# SparkFun_WiFi_Shield_-_DA16200.net
KiCad netlist of a schematic drawn in EAGLE
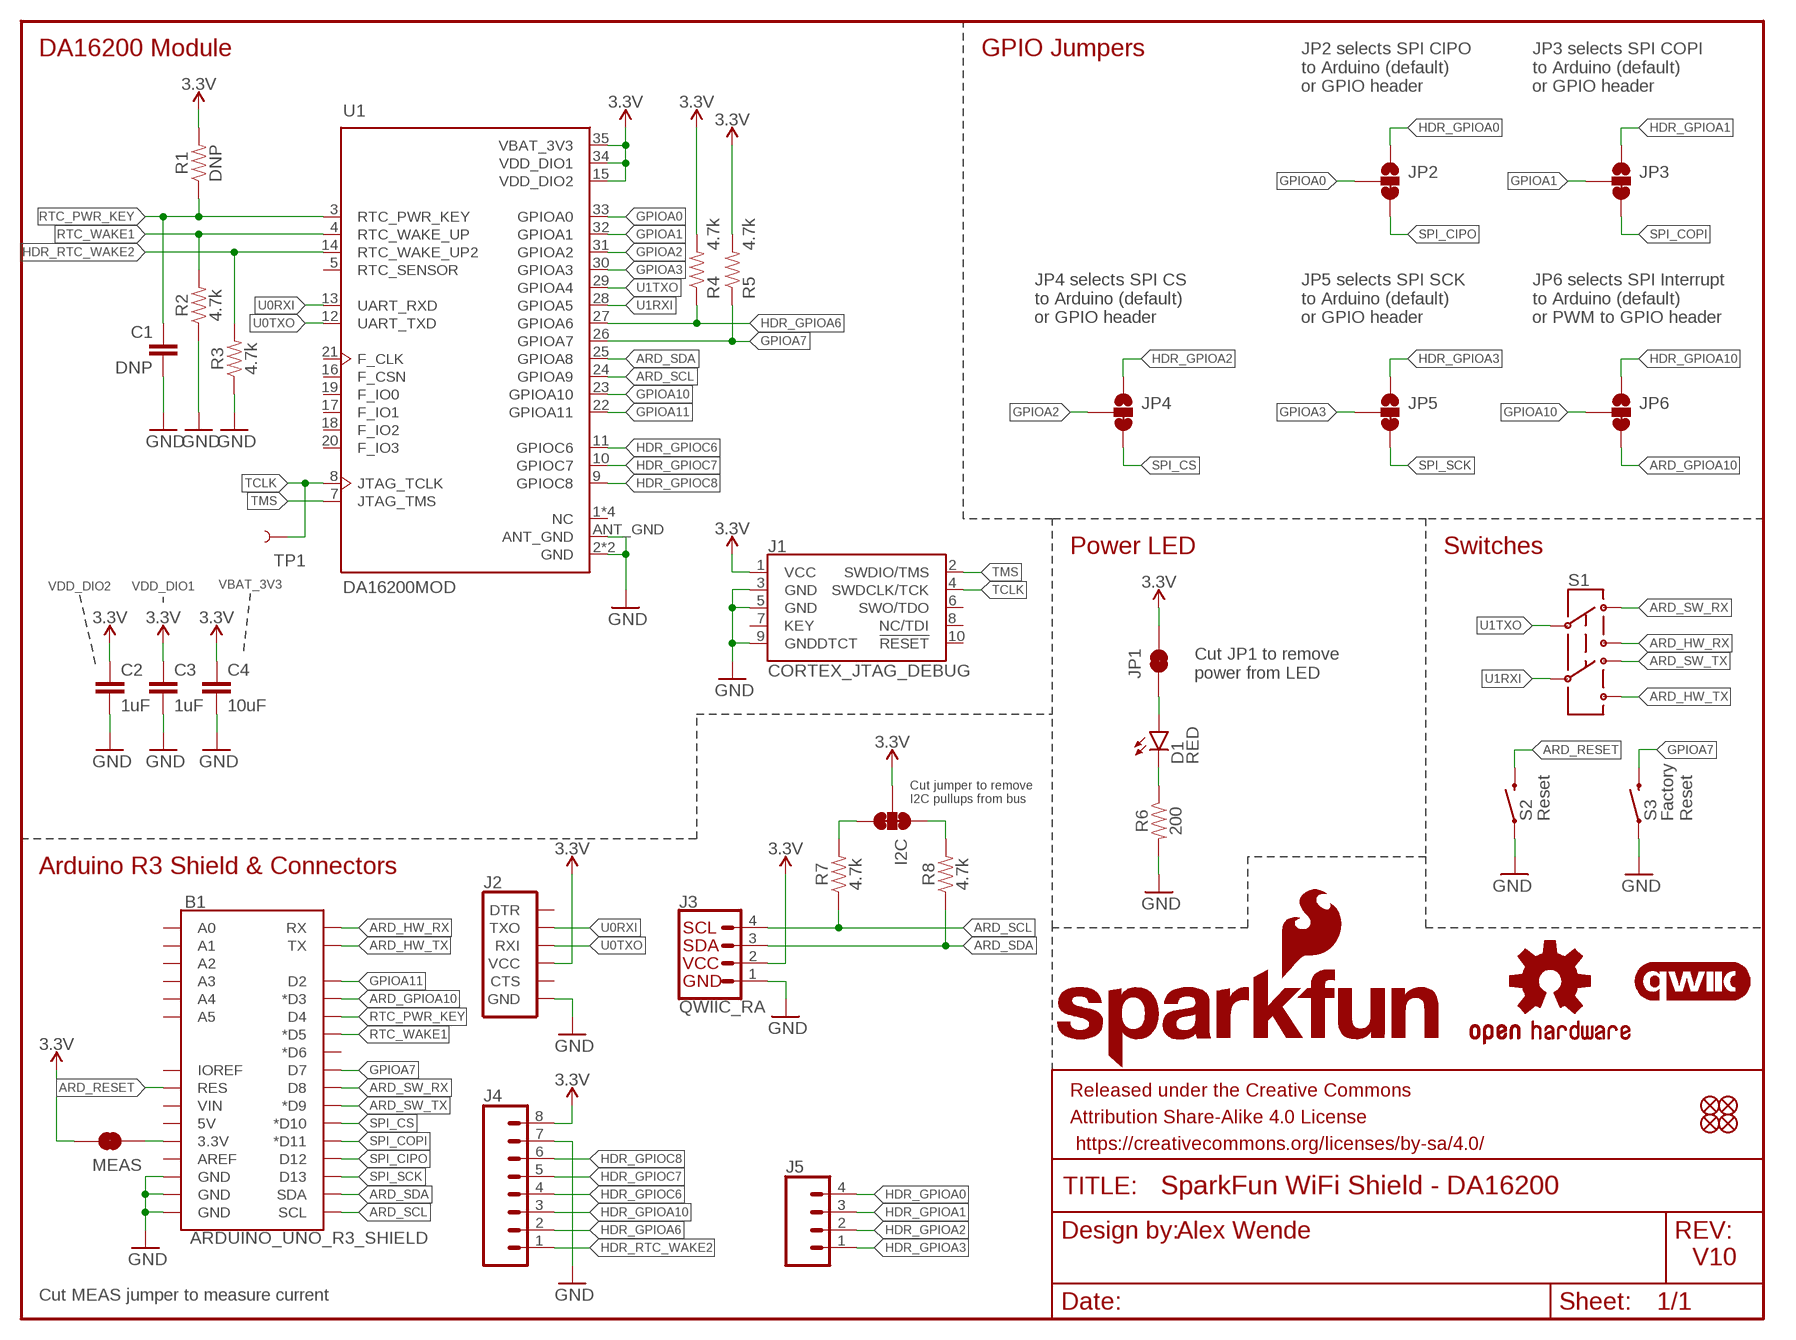
[diagram p0: schematic, sheet 1]

(export (version "E")
  (design (tool "Eeschema 10.0.6"))
  (components
    (comp (ref "B1")
      (value "ARDUINO_UNO_R3_SHIELD")
      (footprint "eagle-import:UNO_R3_SHIELD_NOLABELS_LOCK")
      (libsource (lib "eagle-import") (part "ARDUINO_UNO_R3_SHIELDUNO_R3_SHIELD_NOLABELS_LOCK"))
    )
    (comp (ref "C1")
      (value "DNP")
      (footprint "eagle-import:0603")
      (libsource (lib "eagle-import") (part "CAP-0603"))
    )
    (comp (ref "C2")
      (value "1uF")
      (footprint "eagle-import:0603")
      (libsource (lib "eagle-import") (part "1.0UF-0603-16V-10%"))
    )
    (comp (ref "C3")
      (value "1uF")
      (footprint "eagle-import:0603")
      (libsource (lib "eagle-import") (part "1.0UF-0603-16V-10%"))
    )
    (comp (ref "C4")
      (value "10uF")
      (footprint "eagle-import:0603")
      (libsource (lib "eagle-import") (part "10UF-0603-6.3V-20%"))
    )
    (comp (ref "D1")
      (value "RED")
      (footprint "eagle-import:LED-0603")
      (libsource (lib "eagle-import") (part "LED-RED0603"))
    )
    (comp (ref "FD1")
      (value "FIDUCIAL1X2")
      (footprint "eagle-import:FIDUCIAL-1X2")
      (libsource (lib "eagle-import") (part "FIDUCIAL1X2"))
    )
    (comp (ref "FD2")
      (value "FIDUCIAL1X2")
      (footprint "eagle-import:FIDUCIAL-1X2")
      (libsource (lib "eagle-import") (part "FIDUCIAL1X2"))
    )
    (comp (ref "FD3")
      (value "FIDUCIAL1X2")
      (footprint "eagle-import:FIDUCIAL-1X2")
      (libsource (lib "eagle-import") (part "FIDUCIAL1X2"))
    )
    (comp (ref "FD4")
      (value "FIDUCIAL1X2")
      (footprint "eagle-import:FIDUCIAL-1X2")
      (libsource (lib "eagle-import") (part "FIDUCIAL1X2"))
    )
    (comp (ref "FRAME1")
      (value "FRAME-LETTER")
      (footprint "eagle-import:CREATIVE_COMMONS")
      (libsource (lib "eagle-import") (part "FRAME-LETTER"))
    )
    (comp (ref "I2C")
      (value "JUMPER-SMT_3_2-NC_TRACE_SILK")
      (footprint "eagle-import:SMT-JUMPER_3_2-NC_TRACE_SILK")
      (libsource (lib "eagle-import") (part "JUMPER-SMT_3_2-NC_TRACE_SILK"))
    )
    (comp (ref "J1")
      (value "CORTEX_JTAG_DEBUG")
      (footprint "eagle-import:2X5-PTH-1.27MM-NO_SILK")
      (libsource (lib "eagle-import") (part "CORTEX_JTAG_DEBUG_PTH_NS"))
    )
    (comp (ref "J2")
      (value "6_PIN_SERIAL_TARGET_NO_SILK")
      (footprint "eagle-import:1X06_NO_SILK")
      (libsource (lib "eagle-import") (part "6_PIN_SERIAL_TARGET_NO_SILK"))
    )
    (comp (ref "J3")
      (value "QWIIC_RA")
      (footprint "eagle-import:JST04_1MM_RA")
      (libsource (lib "eagle-import") (part "QWIIC_CONNECTORJS-1MM"))
    )
    (comp (ref "J4")
      (value "CONN_08NO_SILK_DNP")
      (footprint "eagle-import:1X08_NO_SILK")
      (libsource (lib "eagle-import") (part "CONN_08NO_SILK_DNP"))
    )
    (comp (ref "J5")
      (value "CONN_041X04_NO_SILK")
      (footprint "eagle-import:1X04_NO_SILK")
      (libsource (lib "eagle-import") (part "CONN_041X04_NO_SILK"))
    )
    (comp (ref "JP1")
      (value "JUMPER-SMT_2_NC_TRACE_SILK")
      (footprint "eagle-import:SMT-JUMPER_2_NC_TRACE_SILK")
      (libsource (lib "eagle-import") (part "JUMPER-SMT_2_NC_TRACE_SILK"))
    )
    (comp (ref "JP2")
      (value "JUMPER-SMT_3_1-NC_TRACE_SILK")
      (footprint "eagle-import:SMT-JUMPER_3_1-NC_TRACE_SILK")
      (libsource (lib "eagle-import") (part "JUMPER-SMT_3_1-NC_TRACE_SILK"))
    )
    (comp (ref "JP3")
      (value "JUMPER-SMT_3_1-NC_TRACE_SILK")
      (footprint "eagle-import:SMT-JUMPER_3_1-NC_TRACE_SILK")
      (libsource (lib "eagle-import") (part "JUMPER-SMT_3_1-NC_TRACE_SILK"))
    )
    (comp (ref "JP4")
      (value "JUMPER-SMT_3_1-NC_TRACE_SILK")
      (footprint "eagle-import:SMT-JUMPER_3_1-NC_TRACE_SILK")
      (libsource (lib "eagle-import") (part "JUMPER-SMT_3_1-NC_TRACE_SILK"))
    )
    (comp (ref "JP5")
      (value "JUMPER-SMT_3_1-NC_TRACE_SILK")
      (footprint "eagle-import:SMT-JUMPER_3_1-NC_TRACE_SILK")
      (libsource (lib "eagle-import") (part "JUMPER-SMT_3_1-NC_TRACE_SILK"))
    )
    (comp (ref "JP6")
      (value "JUMPER-SMT_3_1-NC_TRACE_SILK")
      (footprint "eagle-import:SMT-JUMPER_3_1-NC_TRACE_SILK")
      (libsource (lib "eagle-import") (part "JUMPER-SMT_3_1-NC_TRACE_SILK"))
    )
    (comp (ref "LOGO1")
      (value "SFE_LOGO_NAME_FLAME.2_INCH")
      (footprint "eagle-import:SFE_LOGO_NAME_FLAME_.2")
      (libsource (lib "eagle-import") (part "SFE_LOGO_NAME_FLAME.2_INCH"))
    )
    (comp (ref "LOGO2")
      (value "OSHW-LOGOM")
      (footprint "eagle-import:OSHW-LOGO-M")
      (libsource (lib "eagle-import") (part "OSHW-LOGOM"))
    )
    (comp (ref "LOGO4")
      (value "QWIIC_LOGO_5MM")
      (footprint "eagle-import:QWIIC_5MM")
      (libsource (lib "eagle-import") (part "QWIIC_LOGO_5MM"))
    )
    (comp (ref "MEAS")
      (value "JUMPER-COMBO_2_NC_TRACE")
      (footprint "eagle-import:COMBO-JUMPER_2_NC_TRACE")
      (libsource (lib "eagle-import") (part "JUMPER-COMBO_2_NC_TRACE"))
    )
    (comp (ref "R1")
      (value "DNP")
      (footprint "eagle-import:0603")
      (libsource (lib "eagle-import") (part "RESISTOR0603"))
    )
    (comp (ref "R2")
      (value "4.7k")
      (footprint "eagle-import:0603")
      (libsource (lib "eagle-import") (part "4.7KOHM-0603-1/10W-1%"))
    )
    (comp (ref "R3")
      (value "4.7k")
      (footprint "eagle-import:0603")
      (libsource (lib "eagle-import") (part "4.7KOHM-0603-1/10W-1%"))
    )
    (comp (ref "R4")
      (value "4.7k")
      (footprint "eagle-import:0603")
      (libsource (lib "eagle-import") (part "4.7KOHM-0603-1/10W-1%"))
    )
    (comp (ref "R5")
      (value "4.7k")
      (footprint "eagle-import:0603")
      (libsource (lib "eagle-import") (part "4.7KOHM-0603-1/10W-1%"))
    )
    (comp (ref "R6")
      (value "200")
      (footprint "eagle-import:0603")
      (libsource (lib "eagle-import") (part "200OHM-0603-1/10W-1%"))
    )
    (comp (ref "R7")
      (value "4.7k")
      (footprint "eagle-import:0603")
      (libsource (lib "eagle-import") (part "4.7KOHM-0603-1/10W-1%"))
    )
    (comp (ref "R8")
      (value "4.7k")
      (footprint "eagle-import:0603")
      (libsource (lib "eagle-import") (part "4.7KOHM-0603-1/10W-1%"))
    )
    (comp (ref "S1")
      (value "DPDT")
      (footprint "eagle-import:SWITCH_DPDT_SMD_AYZ0202")
      (libsource (lib "eagle-import") (part "SWITCH-DPDT-SMD-AYZ0202"))
    )
    (comp (ref "S2")
      (value "Reset")
      (footprint "eagle-import:TACTILE_SWITCH_SMD_5.2MM")
      (libsource (lib "eagle-import") (part "MOMENTARY-SWITCH-SPST-SMD-5.2MM-TALL"))
    )
    (comp (ref "S3")
      (value "MOMENTARY-SWITCH-SPST-SMD-5.2MM-TALL")
      (footprint "eagle-import:TACTILE_SWITCH_SMD_5.2MM")
      (libsource (lib "eagle-import") (part "MOMENTARY-SWITCH-SPST-SMD-5.2MM-TALL"))
    )
    (comp (ref "TP1")
      (value "TEST-POINT3")
      (footprint "eagle-import:PAD.03X.03")
      (libsource (lib "eagle-import") (part "TEST-POINT3"))
    )
    (comp (ref "U1")
      (value "DA16200MOD")
      (footprint "eagle-import:XCVR_DA16200MOD-AAC4WA32")
      (libsource (lib "eagle-import") (part "DA16200MOD-AAC4WA32"))
    )
  )
  (nets
    (net (code "1") (name "3.3V") (class "Default")
      (node (ref "C2") (pin "1") (pinfunction "1_1") (pintype "passive"))
      (node (ref "C3") (pin "1") (pinfunction "1_1") (pintype "passive"))
      (node (ref "C4") (pin "1") (pinfunction "1_1") (pintype "passive"))
      (node (ref "I2C") (pin "2") (pinfunction "2_2") (pintype "passive"))
      (node (ref "J1") (pin "1") (pinfunction "VCC_1") (pintype "bidirectional"))
      (node (ref "J2") (pin "4") (pinfunction "VCC_4") (pintype "passive"))
      (node (ref "J3") (pin "2") (pinfunction "2_2") (pintype "power_in"))
      (node (ref "J4") (pin "8") (pinfunction "8_8") (pintype "passive"))
      (node (ref "JP1") (pin "2") (pinfunction "2_2") (pintype "passive"))
      (node (ref "MEAS") (pin "1") (pinfunction "1_1") (pintype "passive"))
      (node (ref "MEAS") (pin "3") (pinfunction "1_3") (pintype "passive"))
      (node (ref "R1") (pin "2") (pinfunction "2_2") (pintype "passive"))
      (node (ref "R4") (pin "2") (pinfunction "2_2") (pintype "passive"))
      (node (ref "R5") (pin "2") (pinfunction "2_2") (pintype "passive"))
      (node (ref "U1") (pin "15") (pinfunction "VDD_DIO2_15") (pintype "power_in"))
      (node (ref "U1") (pin "34") (pinfunction "VDD_DIO1_34") (pintype "power_in"))
      (node (ref "U1") (pin "35") (pinfunction "VBAT_3V3_35") (pintype "power_in"))
    )
    (net (code "2") (name "ARD_GPIOA10") (class "Default")
      (node (ref "B1") (pin "D3") (pinfunction "*D3_D3") (pintype "bidirectional"))
      (node (ref "JP6") (pin "3") (pinfunction "3_3") (pintype "passive"))
    )
    (net (code "3") (name "ARD_HW_RX") (class "Default")
      (node (ref "B1") (pin "RX") (pinfunction "RX_RX") (pintype "bidirectional"))
      (node (ref "S1") (pin "1") (pinfunction "1_1") (pintype "bidirectional"))
    )
    (net (code "4") (name "ARD_HW_TX") (class "Default")
      (node (ref "B1") (pin "TX") (pinfunction "TX_TX") (pintype "bidirectional"))
      (node (ref "S1") (pin "4") (pinfunction "4_4") (pintype "bidirectional"))
    )
    (net (code "5") (name "ARD_RESET") (class "Default")
      (node (ref "B1") (pin "RES") (pinfunction "RES_RES") (pintype "bidirectional"))
      (node (ref "S2") (pin "3") (pinfunction "2_3") (pintype "passive"))
    )
    (net (code "6") (name "ARD_SCL") (class "Default")
      (node (ref "B1") (pin "SCL") (pinfunction "SCL_SCL") (pintype "bidirectional"))
      (node (ref "J3") (pin "4") (pinfunction "4_4") (pintype "passive"))
      (node (ref "R7") (pin "1") (pinfunction "1_1") (pintype "passive"))
      (node (ref "U1") (pin "24") (pinfunction "GPIOA9_24") (pintype "bidirectional"))
    )
    (net (code "7") (name "ARD_SDA") (class "Default")
      (node (ref "B1") (pin "SDA") (pinfunction "SDA_SDA") (pintype "bidirectional"))
      (node (ref "J3") (pin "3") (pinfunction "3_3") (pintype "passive"))
      (node (ref "R8") (pin "1") (pinfunction "1_1") (pintype "passive"))
      (node (ref "U1") (pin "25") (pinfunction "GPIOA8_25") (pintype "bidirectional"))
    )
    (net (code "8") (name "ARD_SW_RX") (class "Default")
      (node (ref "B1") (pin "D8") (pinfunction "D8_D8") (pintype "bidirectional"))
      (node (ref "S1") (pin "3") (pinfunction "3_3") (pintype "bidirectional"))
    )
    (net (code "9") (name "ARD_SW_TX") (class "Default")
      (node (ref "B1") (pin "D9") (pinfunction "*D9_D9") (pintype "bidirectional"))
      (node (ref "S1") (pin "6") (pinfunction "6_6") (pintype "bidirectional"))
    )
    (net (code "10") (name "GND") (class "Default")
      (node (ref "B1") (pin "GND@0") (pinfunction "GND_GND@0") (pintype "bidirectional"))
      (node (ref "B1") (pin "GND@1") (pinfunction "GND_GND@1") (pintype "bidirectional"))
      (node (ref "B1") (pin "GND@2") (pinfunction "GND_GND@2") (pintype "bidirectional"))
      (node (ref "C1") (pin "2") (pinfunction "2_2") (pintype "passive"))
      (node (ref "C2") (pin "2") (pinfunction "2_2") (pintype "passive"))
      (node (ref "C3") (pin "2") (pinfunction "2_2") (pintype "passive"))
      (node (ref "C4") (pin "2") (pinfunction "2_2") (pintype "passive"))
      (node (ref "J1") (pin "3") (pinfunction "GND_3") (pintype "bidirectional"))
      (node (ref "J1") (pin "5") (pinfunction "GND_5") (pintype "bidirectional"))
      (node (ref "J1") (pin "9") (pinfunction "GNDDTCT_9") (pintype "bidirectional"))
      (node (ref "J2") (pin "6") (pinfunction "GND_6") (pintype "passive"))
      (node (ref "J3") (pin "1") (pinfunction "1_1") (pintype "power_in"))
      (node (ref "J4") (pin "7") (pinfunction "7_7") (pintype "passive"))
      (node (ref "R2") (pin "1") (pinfunction "1_1") (pintype "passive"))
      (node (ref "R3") (pin "1") (pinfunction "1_1") (pintype "passive"))
      (node (ref "R6") (pin "2") (pinfunction "2_2") (pintype "passive"))
      (node (ref "S2") (pin "1") (pinfunction "1_1") (pintype "passive"))
      (node (ref "S3") (pin "1") (pinfunction "1_1") (pintype "passive"))
      (node (ref "U1") (pin "2") (pinfunction "GND_2") (pintype "power_in"))
      (node (ref "U1") (pin "ANT_GND") (pinfunction "ANT_GND_ANT_GND") (pintype "power_in"))
      (node (ref "U1") (pin "GND") (pinfunction "GND_GND") (pintype "power_in"))
    )
    (net (code "11") (name "GPIOA0") (class "Default")
      (node (ref "JP2") (pin "2") (pinfunction "2_2") (pintype "passive"))
      (node (ref "U1") (pin "33") (pinfunction "GPIOA0_33") (pintype "bidirectional"))
    )
    (net (code "12") (name "GPIOA1") (class "Default")
      (node (ref "JP3") (pin "2") (pinfunction "2_2") (pintype "passive"))
      (node (ref "U1") (pin "32") (pinfunction "GPIOA1_32") (pintype "bidirectional"))
    )
    (net (code "13") (name "GPIOA2") (class "Default")
      (node (ref "JP4") (pin "2") (pinfunction "2_2") (pintype "passive"))
      (node (ref "U1") (pin "31") (pinfunction "GPIOA2_31") (pintype "bidirectional"))
    )
    (net (code "14") (name "GPIOA3") (class "Default")
      (node (ref "JP5") (pin "2") (pinfunction "2_2") (pintype "passive"))
      (node (ref "U1") (pin "30") (pinfunction "GPIOA3_30") (pintype "bidirectional"))
    )
    (net (code "15") (name "GPIOA7") (class "Default")
      (node (ref "B1") (pin "D7") (pinfunction "D7_D7") (pintype "bidirectional"))
      (node (ref "R5") (pin "1") (pinfunction "1_1") (pintype "passive"))
      (node (ref "S3") (pin "3") (pinfunction "2_3") (pintype "passive"))
      (node (ref "U1") (pin "26") (pinfunction "GPIOA7_26") (pintype "bidirectional"))
    )
    (net (code "16") (name "GPIOA10") (class "Default")
      (node (ref "JP6") (pin "2") (pinfunction "2_2") (pintype "passive"))
      (node (ref "U1") (pin "23") (pinfunction "GPIOA10_23") (pintype "bidirectional"))
    )
    (net (code "17") (name "GPIOA11") (class "Default")
      (node (ref "B1") (pin "D2") (pinfunction "D2_D2") (pintype "bidirectional"))
      (node (ref "U1") (pin "22") (pinfunction "GPIOA11_22") (pintype "bidirectional"))
    )
    (net (code "18") (name "HDR_GPIOA0") (class "Default")
      (node (ref "J5") (pin "4") (pinfunction "4_4") (pintype "passive"))
      (node (ref "JP2") (pin "1") (pinfunction "1_1") (pintype "passive"))
    )
    (net (code "19") (name "HDR_GPIOA1") (class "Default")
      (node (ref "J5") (pin "3") (pinfunction "3_3") (pintype "passive"))
      (node (ref "JP3") (pin "1") (pinfunction "1_1") (pintype "passive"))
    )
    (net (code "20") (name "HDR_GPIOA2") (class "Default")
      (node (ref "J5") (pin "2") (pinfunction "2_2") (pintype "passive"))
      (node (ref "JP4") (pin "1") (pinfunction "1_1") (pintype "passive"))
    )
    (net (code "21") (name "HDR_GPIOA3") (class "Default")
      (node (ref "J5") (pin "1") (pinfunction "1_1") (pintype "passive"))
      (node (ref "JP5") (pin "1") (pinfunction "1_1") (pintype "passive"))
    )
    (net (code "22") (name "HDR_GPIOA6") (class "Default")
      (node (ref "J4") (pin "2") (pinfunction "2_2") (pintype "passive"))
      (node (ref "R4") (pin "1") (pinfunction "1_1") (pintype "passive"))
      (node (ref "U1") (pin "27") (pinfunction "GPIOA6_27") (pintype "bidirectional"))
    )
    (net (code "23") (name "HDR_GPIOA10") (class "Default")
      (node (ref "J4") (pin "3") (pinfunction "3_3") (pintype "passive"))
      (node (ref "JP6") (pin "1") (pinfunction "1_1") (pintype "passive"))
    )
    (net (code "24") (name "HDR_GPIOC6") (class "Default")
      (node (ref "J4") (pin "4") (pinfunction "4_4") (pintype "passive"))
      (node (ref "U1") (pin "11") (pinfunction "GPIOC6_11") (pintype "bidirectional"))
    )
    (net (code "25") (name "HDR_GPIOC7") (class "Default")
      (node (ref "J4") (pin "5") (pinfunction "5_5") (pintype "passive"))
      (node (ref "U1") (pin "10") (pinfunction "GPIOC7_10") (pintype "bidirectional"))
    )
    (net (code "26") (name "HDR_GPIOC8") (class "Default")
      (node (ref "J4") (pin "6") (pinfunction "6_6") (pintype "passive"))
      (node (ref "U1") (pin "9") (pinfunction "GPIOC8_9") (pintype "bidirectional"))
    )
    (net (code "27") (name "HDR_RTC_WAKE2") (class "Default")
      (node (ref "J4") (pin "1") (pinfunction "1_1") (pintype "passive"))
      (node (ref "R3") (pin "2") (pinfunction "2_2") (pintype "passive"))
      (node (ref "U1") (pin "14") (pinfunction "RTC_WAKE_UP2_14") (pintype "input"))
    )
    (net (code "28") (name "Net-(B1-Pad3.3V)") (class "Default")
      (node (ref "B1") (pin "3.3V") (pinfunction "3.3V_3.3V") (pintype "bidirectional"))
      (node (ref "MEAS") (pin "2") (pinfunction "2_2") (pintype "passive"))
      (node (ref "MEAS") (pin "4") (pinfunction "2_4") (pintype "passive"))
    )
    (net (code "29") (name "Net-(D1-PadA)") (class "Default")
      (node (ref "D1") (pin "A") (pinfunction "A_A") (pintype "passive"))
      (node (ref "JP1") (pin "1") (pinfunction "1_1") (pintype "passive"))
    )
    (net (code "30") (name "Net-(D1-PadC)") (class "Default")
      (node (ref "D1") (pin "C") (pinfunction "C_C") (pintype "passive"))
      (node (ref "R6") (pin "1") (pinfunction "1_1") (pintype "passive"))
    )
    (net (code "31") (name "Net-(I2C-Pad1)") (class "Default")
      (node (ref "I2C") (pin "1") (pinfunction "1_1") (pintype "passive"))
      (node (ref "R8") (pin "2") (pinfunction "2_2") (pintype "passive"))
    )
    (net (code "32") (name "Net-(I2C-Pad3)") (class "Default")
      (node (ref "I2C") (pin "3") (pinfunction "3_3") (pintype "passive"))
      (node (ref "R7") (pin "2") (pinfunction "2_2") (pintype "passive"))
    )
    (net (code "33") (name "RTC_PWR_KEY") (class "Default")
      (node (ref "B1") (pin "D4") (pinfunction "D4_D4") (pintype "bidirectional"))
      (node (ref "C1") (pin "1") (pinfunction "1_1") (pintype "passive"))
      (node (ref "R1") (pin "1") (pinfunction "1_1") (pintype "passive"))
      (node (ref "U1") (pin "3") (pinfunction "RTC_PWR_KEY_3") (pintype "input"))
    )
    (net (code "34") (name "RTC_WAKE1") (class "Default")
      (node (ref "B1") (pin "D5") (pinfunction "*D5_D5") (pintype "bidirectional"))
      (node (ref "R2") (pin "2") (pinfunction "2_2") (pintype "passive"))
      (node (ref "U1") (pin "4") (pinfunction "RTC_WAKE_UP_4") (pintype "input"))
    )
    (net (code "35") (name "SPI_CIPO") (class "Default")
      (node (ref "B1") (pin "D12") (pinfunction "D12_D12") (pintype "bidirectional"))
      (node (ref "JP2") (pin "3") (pinfunction "3_3") (pintype "passive"))
    )
    (net (code "36") (name "SPI_COPI") (class "Default")
      (node (ref "B1") (pin "D11") (pinfunction "*D11_D11") (pintype "bidirectional"))
      (node (ref "JP3") (pin "3") (pinfunction "3_3") (pintype "passive"))
    )
    (net (code "37") (name "SPI_CS") (class "Default")
      (node (ref "B1") (pin "D10") (pinfunction "*D10_D10") (pintype "bidirectional"))
      (node (ref "JP4") (pin "3") (pinfunction "3_3") (pintype "passive"))
    )
    (net (code "38") (name "SPI_SCK") (class "Default")
      (node (ref "B1") (pin "D13") (pinfunction "D13_D13") (pintype "bidirectional"))
      (node (ref "JP5") (pin "3") (pinfunction "3_3") (pintype "passive"))
    )
    (net (code "39") (name "TCLK") (class "Default")
      (node (ref "J1") (pin "4") (pinfunction "SWDCLK/TCK_4") (pintype "bidirectional"))
      (node (ref "TP1") (pin "1") (pinfunction "1_1") (pintype "bidirectional"))
      (node (ref "U1") (pin "8") (pinfunction "JTAG_TCLK_8") (pintype "bidirectional"))
    )
    (net (code "40") (name "TMS") (class "Default")
      (node (ref "J1") (pin "2") (pinfunction "SWDIO/TMS_2") (pintype "bidirectional"))
      (node (ref "U1") (pin "7") (pinfunction "JTAG_TMS_7") (pintype "bidirectional"))
    )
    (net (code "41") (name "U0RXI") (class "Default")
      (node (ref "J2") (pin "3") (pinfunction "TXO_3") (pintype "passive"))
      (node (ref "U1") (pin "13") (pinfunction "UART_RXD_13") (pintype "input"))
    )
    (net (code "42") (name "U0TXO") (class "Default")
      (node (ref "J2") (pin "2") (pinfunction "RXI_2") (pintype "passive"))
      (node (ref "U1") (pin "12") (pinfunction "UART_TXD_12") (pintype "output"))
    )
    (net (code "43") (name "U1RXI") (class "Default")
      (node (ref "S1") (pin "5") (pinfunction "5_5") (pintype "bidirectional"))
      (node (ref "U1") (pin "28") (pinfunction "GPIOA5_28") (pintype "bidirectional"))
    )
    (net (code "44") (name "U1TXO") (class "Default")
      (node (ref "S1") (pin "2") (pinfunction "2_2") (pintype "bidirectional"))
      (node (ref "U1") (pin "29") (pinfunction "GPIOA4_29") (pintype "bidirectional"))
    )
    (net (code "45") (name "unconnected-(B1-*D6-PadD6)") (class "Default")
      (node (ref "B1") (pin "D6") (pinfunction "*D6_D6") (pintype "bidirectional"))
    )
    (net (code "46") (name "unconnected-(B1-Pad5V)") (class "Default")
      (node (ref "B1") (pin "5V") (pinfunction "5V_5V") (pintype "bidirectional"))
    )
    (net (code "47") (name "unconnected-(B1-PadA0)") (class "Default")
      (node (ref "B1") (pin "A0") (pinfunction "A0_A0") (pintype "bidirectional"))
    )
    (net (code "48") (name "unconnected-(B1-PadA1)") (class "Default")
      (node (ref "B1") (pin "A1") (pinfunction "A1_A1") (pintype "bidirectional"))
    )
    (net (code "49") (name "unconnected-(B1-PadA2)") (class "Default")
      (node (ref "B1") (pin "A2") (pinfunction "A2_A2") (pintype "bidirectional"))
    )
    (net (code "50") (name "unconnected-(B1-PadA3)") (class "Default")
      (node (ref "B1") (pin "A3") (pinfunction "A3_A3") (pintype "bidirectional"))
    )
    (net (code "51") (name "unconnected-(B1-PadA4)") (class "Default")
      (node (ref "B1") (pin "A4") (pinfunction "A4_A4") (pintype "bidirectional"))
    )
    (net (code "52") (name "unconnected-(B1-PadA5)") (class "Default")
      (node (ref "B1") (pin "A5") (pinfunction "A5_A5") (pintype "bidirectional"))
    )
    (net (code "53") (name "unconnected-(B1-PadAREF)") (class "Default")
      (node (ref "B1") (pin "AREF") (pinfunction "AREF_AREF") (pintype "bidirectional"))
    )
    (net (code "54") (name "unconnected-(B1-PadIOREF)") (class "Default")
      (node (ref "B1") (pin "IOREF") (pinfunction "IOREF_IOREF") (pintype "bidirectional"))
    )
    (net (code "55") (name "unconnected-(B1-PadVIN)") (class "Default")
      (node (ref "B1") (pin "VIN") (pinfunction "VIN_VIN") (pintype "bidirectional"))
    )
    (net (code "56") (name "unconnected-(J1-KEY-Pad7)") (class "Default")
      (node (ref "J1") (pin "7") (pinfunction "KEY_7") (pintype "bidirectional"))
    )
    (net (code "57") (name "unconnected-(J1-NC{slash}TDI-Pad8)") (class "Default")
      (node (ref "J1") (pin "8") (pinfunction "NC/TDI_8") (pintype "bidirectional"))
    )
    (net (code "58") (name "unconnected-(J1-SWO{slash}TDO-Pad6)") (class "Default")
      (node (ref "J1") (pin "6") (pinfunction "SWO/TDO_6") (pintype "bidirectional"))
    )
    (net (code "59") (name "unconnected-(J1-~{RESET}-Pad10)") (class "Default")
      (node (ref "J1") (pin "10") (pinfunction "~{RESET}_10") (pintype "bidirectional"))
    )
    (net (code "60") (name "unconnected-(J2-CTS-Pad5)") (class "Default")
      (node (ref "J2") (pin "5") (pinfunction "CTS_5") (pintype "passive"))
    )
    (net (code "61") (name "unconnected-(J2-DTR-Pad1)") (class "Default")
      (node (ref "J2") (pin "1") (pinfunction "DTR_1") (pintype "passive"))
    )
    (net (code "62") (name "unconnected-(U1-F_CLK-Pad21)") (class "Default")
      (node (ref "U1") (pin "21") (pinfunction "F_CLK_21") (pintype "bidirectional"))
    )
    (net (code "63") (name "unconnected-(U1-F_CSN-Pad16)") (class "Default")
      (node (ref "U1") (pin "16") (pinfunction "F_CSN_16") (pintype "bidirectional"))
    )
    (net (code "64") (name "unconnected-(U1-F_IO0-Pad19)") (class "Default")
      (node (ref "U1") (pin "19") (pinfunction "F_IO0_19") (pintype "bidirectional"))
    )
    (net (code "65") (name "unconnected-(U1-F_IO1-Pad17)") (class "Default")
      (node (ref "U1") (pin "17") (pinfunction "F_IO1_17") (pintype "bidirectional"))
    )
    (net (code "66") (name "unconnected-(U1-F_IO2-Pad18)") (class "Default")
      (node (ref "U1") (pin "18") (pinfunction "F_IO2_18") (pintype "bidirectional"))
    )
    (net (code "67") (name "unconnected-(U1-F_IO3-Pad20)") (class "Default")
      (node (ref "U1") (pin "20") (pinfunction "F_IO3_20") (pintype "bidirectional"))
    )
    (net (code "68") (name "unconnected-(U1-NC-Pad1)") (class "Default")
      (node (ref "U1") (pin "1") (pinfunction "NC_1") (pintype "no_connect"))
    )
    (net (code "69") (name "unconnected-(U1-NC-Pad6)") (class "Default")
      (node (ref "U1") (pin "6") (pinfunction "NC_6") (pintype "no_connect"))
    )
    (net (code "70") (name "unconnected-(U1-NC-Pad36)") (class "Default")
      (node (ref "U1") (pin "36") (pinfunction "NC_36") (pintype "no_connect"))
    )
    (net (code "71") (name "unconnected-(U1-NC-Pad37)") (class "Default")
      (node (ref "U1") (pin "37") (pinfunction "NC_37") (pintype "no_connect"))
    )
    (net (code "72") (name "unconnected-(U1-RTC_SENSOR-Pad5)") (class "Default")
      (node (ref "U1") (pin "5") (pinfunction "RTC_SENSOR_5") (pintype "output"))
    )
  )
)
